# telemetry_box.net
KiCad netlist of a schematic drawn in EAGLE
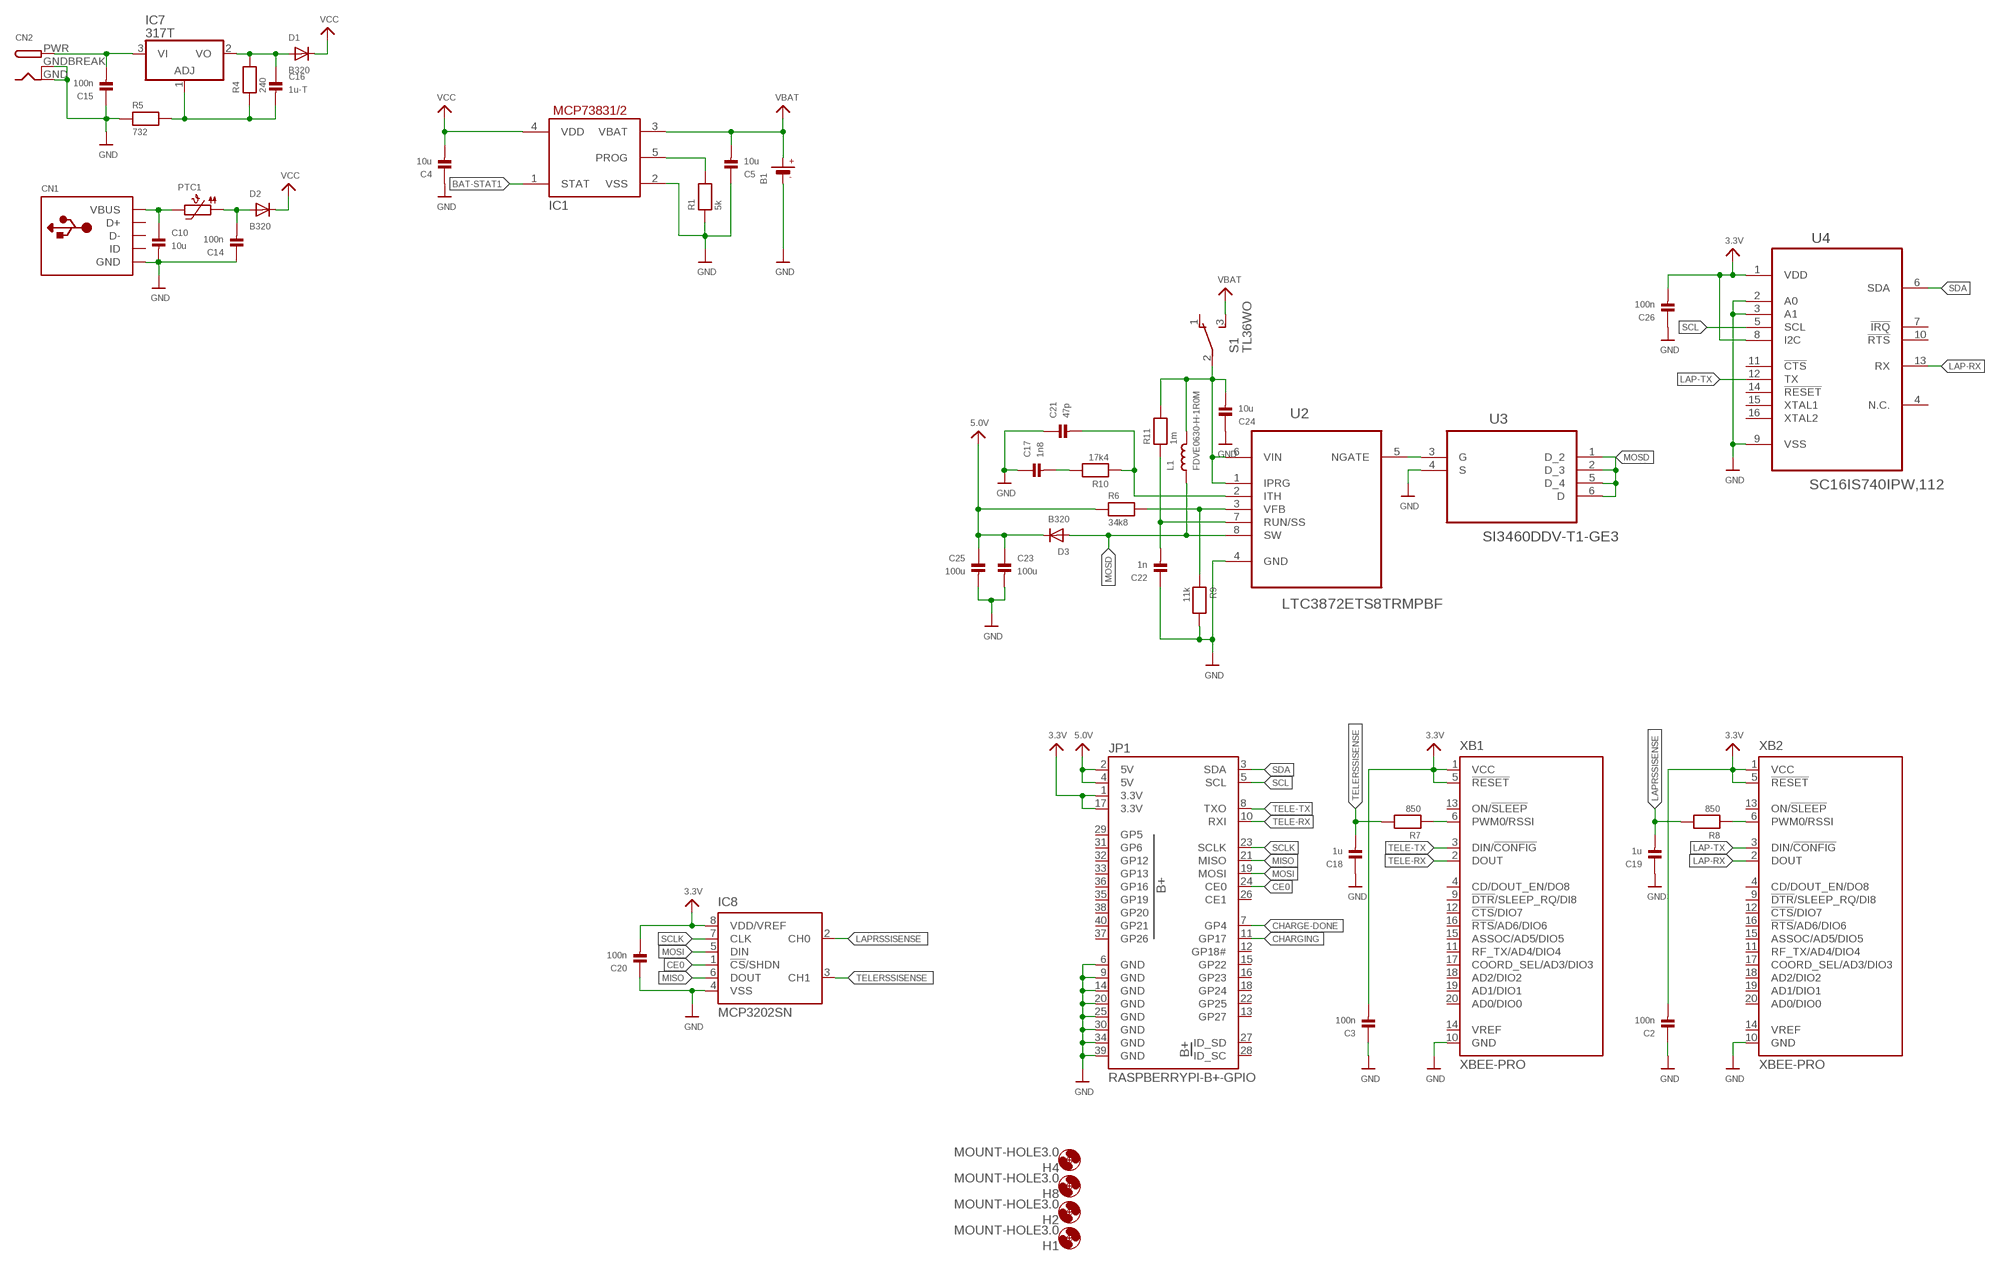
[diagram p0: schematic, sheet 1]

(export (version "E")
  (design (tool "Eeschema 10.0.6"))
  (components
    (comp (ref "B1")
      (value "BATTERY")
      (footprint "eagle-import:JSTPH2")
      (libsource (lib "eagle-import") (part "BATTERY"))
    )
    (comp (ref "C2")
      (value "100n")
      (footprint "eagle-import:_0603")
      (libsource (lib "eagle-import") (part "CAP_CERAMIC_0603"))
    )
    (comp (ref "C3")
      (value "100n")
      (footprint "eagle-import:_0603")
      (libsource (lib "eagle-import") (part "CAP_CERAMIC_0603"))
    )
    (comp (ref "C4")
      (value "10u")
      (footprint "eagle-import:_0805")
      (libsource (lib "eagle-import") (part "CAP_CERAMIC_0805"))
    )
    (comp (ref "C5")
      (value "10u")
      (footprint "eagle-import:_0805")
      (libsource (lib "eagle-import") (part "CAP_CERAMIC_0805"))
    )
    (comp (ref "C10")
      (value "10u")
      (footprint "eagle-import:_0805")
      (libsource (lib "eagle-import") (part "CAP_CERAMIC_0805"))
    )
    (comp (ref "C14")
      (value "100n")
      (footprint "eagle-import:_0603")
      (libsource (lib "eagle-import") (part "CAP_CERAMIC_0603"))
    )
    (comp (ref "C15")
      (value "100n")
      (footprint "eagle-import:_0603")
      (libsource (lib "eagle-import") (part "CAP_CERAMIC_0603"))
    )
    (comp (ref "C16")
      (value "1u-T")
      (footprint "eagle-import:_0603")
      (libsource (lib "eagle-import") (part "CAP_CERAMIC_0603"))
    )
    (comp (ref "C17")
      (value "1n8")
      (footprint "eagle-import:_0603")
      (libsource (lib "eagle-import") (part "CAP_CERAMIC_0603"))
    )
    (comp (ref "C18")
      (value "1u")
      (footprint "eagle-import:_0603")
      (libsource (lib "eagle-import") (part "CAP_CERAMIC_0603"))
    )
    (comp (ref "C19")
      (value "1u")
      (footprint "eagle-import:_0603")
      (libsource (lib "eagle-import") (part "CAP_CERAMIC_0603"))
    )
    (comp (ref "C20")
      (value "100n")
      (footprint "eagle-import:_0603")
      (libsource (lib "eagle-import") (part "CAP_CERAMIC_0603"))
    )
    (comp (ref "C21")
      (value "47p")
      (footprint "eagle-import:_0603")
      (libsource (lib "eagle-import") (part "CAP_CERAMIC_0603"))
    )
    (comp (ref "C22")
      (value "1n")
      (footprint "eagle-import:_0603")
      (libsource (lib "eagle-import") (part "CAP_CERAMIC_0603"))
    )
    (comp (ref "C23")
      (value "100u")
      (footprint "eagle-import:1206")
      (libsource (lib "eagle-import") (part "CAP_CERAMIC1206"))
    )
    (comp (ref "C24")
      (value "10u")
      (footprint "eagle-import:_0805")
      (libsource (lib "eagle-import") (part "CAP_CERAMIC_0805"))
    )
    (comp (ref "C25")
      (value "100u")
      (footprint "eagle-import:1206")
      (libsource (lib "eagle-import") (part "CAP_CERAMIC1206"))
    )
    (comp (ref "C26")
      (value "100n")
      (footprint "eagle-import:_0603")
      (libsource (lib "eagle-import") (part "CAP_CERAMIC_0603"))
    )
    (comp (ref "CN1")
      (value "USBMINIB")
      (footprint "eagle-import:USB-MINIB")
      (libsource (lib "eagle-import") (part "USBMINIB"))
    )
    (comp (ref "CN2")
      (value "DCBARRELPTH")
      (footprint "eagle-import:DCJACK_2MM_PTH")
      (libsource (lib "eagle-import") (part "DCBARRELPTH"))
    )
    (comp (ref "D1")
      (value "B320")
      (footprint "eagle-import:SMADIODE")
      (libsource (lib "eagle-import") (part "DIODESMA"))
    )
    (comp (ref "D2")
      (value "B320")
      (footprint "eagle-import:SMADIODE")
      (libsource (lib "eagle-import") (part "DIODESMA"))
    )
    (comp (ref "D3")
      (value "B320")
      (footprint "eagle-import:SMADIODE")
      (libsource (lib "eagle-import") (part "DIODESMA"))
    )
    (comp (ref "H1")
      (value "MOUNT-HOLE3.0")
      (footprint "eagle-import:3,0")
      (libsource (lib "eagle-import") (part "MOUNT-HOLE3.0"))
    )
    (comp (ref "H2")
      (value "MOUNT-HOLE3.0")
      (footprint "eagle-import:3,0")
      (libsource (lib "eagle-import") (part "MOUNT-HOLE3.0"))
    )
    (comp (ref "H4")
      (value "MOUNT-HOLE3.0")
      (footprint "eagle-import:3,0")
      (libsource (lib "eagle-import") (part "MOUNT-HOLE3.0"))
    )
    (comp (ref "H8")
      (value "MOUNT-HOLE3.0")
      (footprint "eagle-import:3,0")
      (libsource (lib "eagle-import") (part "MOUNT-HOLE3.0"))
    )
    (comp (ref "IC1")
      (value "MCP73831/OT")
      (footprint "eagle-import:SOT23-5L")
      (libsource (lib "eagle-import") (part "MCP73831/OT"))
    )
    (comp (ref "IC7")
      (value "317T")
      (footprint "eagle-import:TO220H")
      (libsource (lib "eagle-import") (part "317T"))
    )
    (comp (ref "IC8")
      (value "MCP3202SN")
      (footprint "eagle-import:SO-08")
      (fields (field (name "MF") "MICROCHIP") (field (name "MPN") "MCP3202-CI/SN"))
      (libsource (lib "eagle-import") (part "MCP3202SN"))
    )
    (comp (ref "JP1")
      (value "RASPBERRYPI-B+-GPIO")
      (footprint "eagle-import:2X20-SHROUDED")
      (libsource (lib "eagle-import") (part "RASPBERRYPI-B+-GPIO"))
    )
    (comp (ref "L1")
      (value "FDVE0630-H-1R0M")
      (footprint "eagle-import:INDUCTOR_6X6MM_TDK_SLF6045")
      (libsource (lib "eagle-import") (part "INDUCTORTDK_SLF6045"))
    )
    (comp (ref "PTC1")
      (value "PTC1206")
      (footprint "eagle-import:1206")
      (libsource (lib "eagle-import") (part "PTC1206"))
    )
    (comp (ref "R1")
      (value "5k")
      (footprint "eagle-import:_0603")
      (libsource (lib "eagle-import") (part "RESISTOR_0603"))
    )
    (comp (ref "R4")
      (value "240")
      (footprint "eagle-import:_0603")
      (libsource (lib "eagle-import") (part "RESISTOR_0603"))
    )
    (comp (ref "R5")
      (value "732")
      (footprint "eagle-import:_0603")
      (libsource (lib "eagle-import") (part "RESISTOR_0603"))
    )
    (comp (ref "R6")
      (value "34k8")
      (footprint "eagle-import:_0603")
      (libsource (lib "eagle-import") (part "RESISTOR_0603"))
    )
    (comp (ref "R7")
      (value "850")
      (footprint "eagle-import:_0603")
      (libsource (lib "eagle-import") (part "RESISTOR_0603"))
    )
    (comp (ref "R8")
      (value "850")
      (footprint "eagle-import:_0603")
      (libsource (lib "eagle-import") (part "RESISTOR_0603"))
    )
    (comp (ref "R9")
      (value "11k")
      (footprint "eagle-import:_0603")
      (libsource (lib "eagle-import") (part "RESISTOR_0603"))
    )
    (comp (ref "R10")
      (value "17k4")
      (footprint "eagle-import:_0603")
      (libsource (lib "eagle-import") (part "RESISTOR_0603"))
    )
    (comp (ref "R11")
      (value "1m")
      (footprint "eagle-import:_0603")
      (libsource (lib "eagle-import") (part "RESISTOR_0603"))
    )
    (comp (ref "S1")
      (value "TL36WO")
      (footprint "eagle-import:TL3XWO")
      (libsource (lib "eagle-import") (part "TL36WO"))
    )
    (comp (ref "U2")
      (value "LTC3872ETS8TRMPBF")
      (footprint "eagle-import:SOT65P280X100-8N")
      (fields (field (name "MPN") "LTC3872ETS8#TRMPBF"))
      (libsource (lib "eagle-import") (part "LTC3872ETS8TRMPBF"))
    )
    (comp (ref "U3")
      (value "SI3460DDV-T1-GE3")
      (footprint "eagle-import:SOT95P285X110-6N")
      (fields (field (name "MPN") "SI3457CDV-T1-GE3"))
      (libsource (lib "eagle-import") (part "SI3457CDV-T1-GE3"))
    )
    (comp (ref "U4")
      (value "SC16IS740IPW,112")
      (footprint "eagle-import:SOP65P640X110-16N")
      (libsource (lib "eagle-import") (part "SC16IS740IPW,112"))
    )
    (comp (ref "XB1")
      (value "XBEE-PRO")
      (footprint "eagle-import:XBEE-PRO")
      (libsource (lib "eagle-import") (part "XBEE-PRO"))
    )
    (comp (ref "XB2")
      (value "XBEE-PRO")
      (footprint "eagle-import:XBEE-PRO")
      (libsource (lib "eagle-import") (part "XBEE-PRO"))
    )
  )
  (nets
    (net (code "1") (name "3.3V") (class "Default")
      (node (ref "C2") (pin "2") (pinfunction "P$2_2") (pintype "passive"))
      (node (ref "C20") (pin "2") (pinfunction "P$2_2") (pintype "passive"))
      (node (ref "C26") (pin "2") (pinfunction "P$2_2") (pintype "passive"))
      (node (ref "C3") (pin "2") (pinfunction "P$2_2") (pintype "passive"))
      (node (ref "IC8") (pin "8") (pinfunction "VDD/VREF_8") (pintype "input"))
      (node (ref "JP1") (pin "1") (pinfunction "3.3V_1") (pintype "power_in"))
      (node (ref "JP1") (pin "17") (pinfunction "3.3V_17") (pintype "power_in"))
      (node (ref "U4") (pin "1") (pinfunction "VDD_1") (pintype "power_in"))
      (node (ref "U4") (pin "8") (pinfunction "I2C_8") (pintype "input"))
      (node (ref "XB1") (pin "1") (pinfunction "VCC_1") (pintype "power_in"))
      (node (ref "XB1") (pin "5") (pinfunction "~{RESET}_5") (pintype "input"))
      (node (ref "XB2") (pin "1") (pinfunction "VCC_1") (pintype "power_in"))
      (node (ref "XB2") (pin "5") (pinfunction "~{RESET}_5") (pintype "input"))
    )
    (net (code "2") (name "5.0V") (class "Default")
      (node (ref "C23") (pin "1") (pinfunction "P$1_1") (pintype "passive"))
      (node (ref "C25") (pin "1") (pinfunction "P$1_1") (pintype "passive"))
      (node (ref "D3") (pin "C") (pinfunction "C_C") (pintype "passive"))
      (node (ref "JP1") (pin "2") (pinfunction "5V_2") (pintype "power_in"))
      (node (ref "JP1") (pin "4") (pinfunction "5V_4") (pintype "power_in"))
      (node (ref "R6") (pin "1") (pinfunction "1_1") (pintype "passive"))
    )
    (net (code "3") (name "BAT-STAT1") (class "Default")
      (node (ref "IC1") (pin "1") (pinfunction "STAT_1") (pintype "output"))
    )
    (net (code "4") (name "CE0") (class "Default")
      (node (ref "IC8") (pin "1") (pinfunction "~{CS}/SHDN_1") (pintype "input"))
      (node (ref "JP1") (pin "24") (pinfunction "CE0_24") (pintype "output"))
    )
    (net (code "5") (name "CHARGE-DONE") (class "Default")
      (node (ref "JP1") (pin "7") (pinfunction "GP4_7") (pintype "bidirectional"))
    )
    (net (code "6") (name "CHARGING") (class "Default")
      (node (ref "JP1") (pin "11") (pinfunction "GP17_11") (pintype "bidirectional"))
    )
    (net (code "7") (name "GND") (class "Default")
      (node (ref "B1") (pin "1") (pinfunction "-_1") (pintype "passive"))
      (node (ref "C10") (pin "2") (pinfunction "P$2_2") (pintype "passive"))
      (node (ref "C14") (pin "1") (pinfunction "P$1_1") (pintype "passive"))
      (node (ref "C15") (pin "1") (pinfunction "P$1_1") (pintype "passive"))
      (node (ref "C17") (pin "1") (pinfunction "P$1_1") (pintype "passive"))
      (node (ref "C18") (pin "1") (pinfunction "P$1_1") (pintype "passive"))
      (node (ref "C19") (pin "1") (pinfunction "P$1_1") (pintype "passive"))
      (node (ref "C2") (pin "1") (pinfunction "P$1_1") (pintype "passive"))
      (node (ref "C20") (pin "1") (pinfunction "P$1_1") (pintype "passive"))
      (node (ref "C21") (pin "1") (pinfunction "P$1_1") (pintype "passive"))
      (node (ref "C22") (pin "1") (pinfunction "P$1_1") (pintype "passive"))
      (node (ref "C23") (pin "2") (pinfunction "P$2_2") (pintype "passive"))
      (node (ref "C24") (pin "1") (pinfunction "P$1_1") (pintype "passive"))
      (node (ref "C25") (pin "2") (pinfunction "P$2_2") (pintype "passive"))
      (node (ref "C26") (pin "1") (pinfunction "P$1_1") (pintype "passive"))
      (node (ref "C3") (pin "1") (pinfunction "P$1_1") (pintype "passive"))
      (node (ref "C4") (pin "1") (pinfunction "P$1_1") (pintype "passive"))
      (node (ref "C5") (pin "1") (pinfunction "P$1_1") (pintype "passive"))
      (node (ref "CN1") (pin "GND") (pinfunction "GND_GND") (pintype "power_in"))
      (node (ref "CN2") (pin "GND") (pinfunction "GND_GND") (pintype "power_in"))
      (node (ref "CN2") (pin "GNDBREAK") (pinfunction "GNDBREAK_GNDBREAK") (pintype "power_in"))
      (node (ref "IC1") (pin "2") (pinfunction "VSS_2") (pintype "power_in"))
      (node (ref "IC8") (pin "4") (pinfunction "VSS_4") (pintype "input"))
      (node (ref "JP1") (pin "14") (pinfunction "GND_14") (pintype "power_in"))
      (node (ref "JP1") (pin "20") (pinfunction "GND_20") (pintype "power_in"))
      (node (ref "JP1") (pin "25") (pinfunction "GND_25") (pintype "power_in"))
      (node (ref "JP1") (pin "30") (pinfunction "GND_30") (pintype "power_in"))
      (node (ref "JP1") (pin "34") (pinfunction "GND_34") (pintype "power_in"))
      (node (ref "JP1") (pin "39") (pinfunction "GND_39") (pintype "power_in"))
      (node (ref "JP1") (pin "6") (pinfunction "GND_6") (pintype "power_in"))
      (node (ref "JP1") (pin "9") (pinfunction "GND_9") (pintype "power_in"))
      (node (ref "R1") (pin "1") (pinfunction "1_1") (pintype "passive"))
      (node (ref "R5") (pin "1") (pinfunction "1_1") (pintype "passive"))
      (node (ref "R9") (pin "2") (pinfunction "2_2") (pintype "passive"))
      (node (ref "U2") (pin "4") (pinfunction "GND_4") (pintype "passive"))
      (node (ref "U3") (pin "4") (pinfunction "S_4") (pintype "passive"))
      (node (ref "U4") (pin "2") (pinfunction "A0_2") (pintype "input"))
      (node (ref "U4") (pin "3") (pinfunction "A1_3") (pintype "input"))
      (node (ref "U4") (pin "9") (pinfunction "VSS_9") (pintype "power_in"))
      (node (ref "XB1") (pin "10") (pinfunction "GND_10") (pintype "power_in"))
      (node (ref "XB2") (pin "10") (pinfunction "GND_10") (pintype "power_in"))
    )
    (net (code "8") (name "LAP-RX") (class "Default")
      (node (ref "U4") (pin "13") (pinfunction "RX_13") (pintype "output"))
      (node (ref "XB2") (pin "2") (pinfunction "DOUT_2") (pintype "output"))
    )
    (net (code "9") (name "LAP-TX") (class "Default")
      (node (ref "U4") (pin "12") (pinfunction "TX_12") (pintype "input"))
      (node (ref "XB2") (pin "3") (pinfunction "DIN/~{CONFIG}_3") (pintype "input"))
    )
    (net (code "10") (name "LAPRSSISENSE") (class "Default")
      (node (ref "C19") (pin "2") (pinfunction "P$2_2") (pintype "passive"))
      (node (ref "IC8") (pin "2") (pinfunction "CH0_2") (pintype "input"))
      (node (ref "R8") (pin "2") (pinfunction "2_2") (pintype "passive"))
    )
    (net (code "11") (name "MISO") (class "Default")
      (node (ref "IC8") (pin "6") (pinfunction "DOUT_6") (pintype "input"))
      (node (ref "JP1") (pin "21") (pinfunction "MISO_21") (pintype "input"))
    )
    (net (code "12") (name "MOSD") (class "Default")
      (node (ref "D3") (pin "A") (pinfunction "A_A") (pintype "passive"))
      (node (ref "L1") (pin "P$1") (pinfunction "1_P$1") (pintype "passive"))
      (node (ref "U2") (pin "8") (pinfunction "SW_8") (pintype "passive"))
      (node (ref "U3") (pin "1") (pinfunction "D_2_1") (pintype "passive"))
      (node (ref "U3") (pin "2") (pinfunction "D_3_2") (pintype "passive"))
      (node (ref "U3") (pin "5") (pinfunction "D_4_5") (pintype "passive"))
      (node (ref "U3") (pin "6") (pinfunction "D_6") (pintype "passive"))
    )
    (net (code "13") (name "MOSI") (class "Default")
      (node (ref "IC8") (pin "5") (pinfunction "DIN_5") (pintype "input"))
      (node (ref "JP1") (pin "19") (pinfunction "MOSI_19") (pintype "output"))
    )
    (net (code "14") (name "Net-(C10-P$1)") (class "Default")
      (node (ref "C10") (pin "1") (pinfunction "P$1_1") (pintype "passive"))
      (node (ref "CN1") (pin "VBUS") (pinfunction "VBUS_VBUS") (pintype "power_in"))
      (node (ref "PTC1") (pin "2") (pinfunction "2_2") (pintype "passive"))
    )
    (net (code "15") (name "Net-(C14-P$2)") (class "Default")
      (node (ref "C14") (pin "2") (pinfunction "P$2_2") (pintype "passive"))
      (node (ref "D2") (pin "A") (pinfunction "A_A") (pintype "passive"))
      (node (ref "PTC1") (pin "1") (pinfunction "1_1") (pintype "passive"))
    )
    (net (code "16") (name "Net-(C15-P$2)") (class "Default")
      (node (ref "C15") (pin "2") (pinfunction "P$2_2") (pintype "passive"))
      (node (ref "CN2") (pin "PWR") (pinfunction "PWR_PWR") (pintype "power_in"))
      (node (ref "IC7") (pin "3") (pinfunction "VI_3") (pintype "input"))
    )
    (net (code "17") (name "Net-(C16-P$1)") (class "Default")
      (node (ref "C16") (pin "1") (pinfunction "P$1_1") (pintype "passive"))
      (node (ref "D1") (pin "A") (pinfunction "A_A") (pintype "passive"))
      (node (ref "IC7") (pin "2") (pinfunction "VO_2") (pintype "passive"))
      (node (ref "R4") (pin "2") (pinfunction "2_2") (pintype "passive"))
    )
    (net (code "18") (name "Net-(C16-P$2)") (class "Default")
      (node (ref "C16") (pin "2") (pinfunction "P$2_2") (pintype "passive"))
      (node (ref "IC7") (pin "1") (pinfunction "ADJ_1") (pintype "input"))
      (node (ref "R4") (pin "1") (pinfunction "1_1") (pintype "passive"))
      (node (ref "R5") (pin "2") (pinfunction "2_2") (pintype "passive"))
    )
    (net (code "19") (name "Net-(C17-P$2)") (class "Default")
      (node (ref "C17") (pin "2") (pinfunction "P$2_2") (pintype "passive"))
      (node (ref "R10") (pin "2") (pinfunction "2_2") (pintype "passive"))
    )
    (net (code "20") (name "Net-(C21-P$2)") (class "Default")
      (node (ref "C21") (pin "2") (pinfunction "P$2_2") (pintype "passive"))
      (node (ref "R10") (pin "1") (pinfunction "1_1") (pintype "passive"))
      (node (ref "U2") (pin "2") (pinfunction "ITH_2") (pintype "input"))
    )
    (net (code "21") (name "Net-(C22-P$2)") (class "Default")
      (node (ref "C22") (pin "2") (pinfunction "P$2_2") (pintype "passive"))
      (node (ref "R11") (pin "1") (pinfunction "1_1") (pintype "passive"))
      (node (ref "U2") (pin "7") (pinfunction "RUN/SS_7") (pintype "input"))
    )
    (net (code "22") (name "Net-(C24-P$2)") (class "Default")
      (node (ref "C24") (pin "2") (pinfunction "P$2_2") (pintype "passive"))
      (node (ref "L1") (pin "P$2") (pinfunction "2_P$2") (pintype "passive"))
      (node (ref "R11") (pin "2") (pinfunction "2_2") (pintype "passive"))
      (node (ref "S1") (pin "2") (pinfunction "P_2") (pintype "passive"))
      (node (ref "U2") (pin "1") (pinfunction "IPRG_1") (pintype "input"))
      (node (ref "U2") (pin "6") (pinfunction "VIN_6") (pintype "power_in"))
    )
    (net (code "23") (name "Net-(IC1-PROG)") (class "Default")
      (node (ref "IC1") (pin "5") (pinfunction "PROG_5") (pintype "input"))
      (node (ref "R1") (pin "2") (pinfunction "2_2") (pintype "passive"))
    )
    (net (code "24") (name "Net-(U2-NGATE)") (class "Default")
      (node (ref "U2") (pin "5") (pinfunction "NGATE_5") (pintype "output"))
      (node (ref "U3") (pin "3") (pinfunction "G_3") (pintype "passive"))
    )
    (net (code "25") (name "Net-(U2-VFB)") (class "Default")
      (node (ref "R6") (pin "2") (pinfunction "2_2") (pintype "passive"))
      (node (ref "R9") (pin "1") (pinfunction "1_1") (pintype "passive"))
      (node (ref "U2") (pin "3") (pinfunction "VFB_3") (pintype "input"))
    )
    (net (code "26") (name "Net-(XB1-PWM0{slash}RSSI)") (class "Default")
      (node (ref "R7") (pin "1") (pinfunction "1_1") (pintype "passive"))
      (node (ref "XB1") (pin "6") (pinfunction "PWM0/RSSI_6") (pintype "output"))
    )
    (net (code "27") (name "Net-(XB2-PWM0{slash}RSSI)") (class "Default")
      (node (ref "R8") (pin "1") (pinfunction "1_1") (pintype "passive"))
      (node (ref "XB2") (pin "6") (pinfunction "PWM0/RSSI_6") (pintype "output"))
    )
    (net (code "28") (name "SCL") (class "Default")
      (node (ref "JP1") (pin "5") (pinfunction "SCL_5") (pintype "bidirectional"))
      (node (ref "U4") (pin "5") (pinfunction "SCL_5") (pintype "input"))
    )
    (net (code "29") (name "SCLK") (class "Default")
      (node (ref "IC8") (pin "7") (pinfunction "CLK_7") (pintype "input"))
      (node (ref "JP1") (pin "23") (pinfunction "SCLK_23") (pintype "output"))
    )
    (net (code "30") (name "SDA") (class "Default")
      (node (ref "JP1") (pin "3") (pinfunction "SDA_3") (pintype "bidirectional"))
      (node (ref "U4") (pin "6") (pinfunction "SDA_6") (pintype "bidirectional"))
    )
    (net (code "31") (name "TELE-RX") (class "Default")
      (node (ref "JP1") (pin "10") (pinfunction "RXI_10") (pintype "input"))
      (node (ref "XB1") (pin "2") (pinfunction "DOUT_2") (pintype "output"))
    )
    (net (code "32") (name "TELE-TX") (class "Default")
      (node (ref "JP1") (pin "8") (pinfunction "TXO_8") (pintype "output"))
      (node (ref "XB1") (pin "3") (pinfunction "DIN/~{CONFIG}_3") (pintype "input"))
    )
    (net (code "33") (name "TELERSSISENSE") (class "Default")
      (node (ref "C18") (pin "2") (pinfunction "P$2_2") (pintype "passive"))
      (node (ref "IC8") (pin "3") (pinfunction "CH1_3") (pintype "input"))
      (node (ref "R7") (pin "2") (pinfunction "2_2") (pintype "passive"))
    )
    (net (code "34") (name "VBAT") (class "Default")
      (node (ref "B1") (pin "2") (pinfunction "+_2") (pintype "passive"))
      (node (ref "C5") (pin "2") (pinfunction "P$2_2") (pintype "passive"))
      (node (ref "IC1") (pin "3") (pinfunction "VBAT_3") (pintype "bidirectional"))
      (node (ref "S1") (pin "3") (pinfunction "S_3") (pintype "passive"))
    )
    (net (code "35") (name "VCC") (class "Default")
      (node (ref "C4") (pin "2") (pinfunction "P$2_2") (pintype "passive"))
      (node (ref "D1") (pin "C") (pinfunction "C_C") (pintype "passive"))
      (node (ref "D2") (pin "C") (pinfunction "C_C") (pintype "passive"))
      (node (ref "IC1") (pin "4") (pinfunction "VDD_4") (pintype "power_in"))
    )
    (net (code "36") (name "unconnected-(CN1-PadD+)") (class "Default")
      (node (ref "CN1") (pin "D+") (pinfunction "D+_D+") (pintype "bidirectional"))
    )
    (net (code "37") (name "unconnected-(CN1-PadD-)") (class "Default")
      (node (ref "CN1") (pin "D-") (pinfunction "D-_D-") (pintype "bidirectional"))
    )
    (net (code "38") (name "unconnected-(CN1-PadID)") (class "Default")
      (node (ref "CN1") (pin "ID") (pinfunction "ID_ID") (pintype "bidirectional"))
    )
    (net (code "39") (name "unconnected-(JP1-CE1-Pad26)") (class "Default")
      (node (ref "JP1") (pin "26") (pinfunction "CE1_26") (pintype "output"))
    )
    (net (code "40") (name "unconnected-(JP1-GP5-Pad29)") (class "Default")
      (node (ref "JP1") (pin "29") (pinfunction "GP5_29") (pintype "bidirectional"))
    )
    (net (code "41") (name "unconnected-(JP1-GP6-Pad31)") (class "Default")
      (node (ref "JP1") (pin "31") (pinfunction "GP6_31") (pintype "bidirectional"))
    )
    (net (code "42") (name "unconnected-(JP1-GP12-Pad32)") (class "Default")
      (node (ref "JP1") (pin "32") (pinfunction "GP12_32") (pintype "bidirectional"))
    )
    (net (code "43") (name "unconnected-(JP1-GP13-Pad33)") (class "Default")
      (node (ref "JP1") (pin "33") (pinfunction "GP13_33") (pintype "bidirectional"))
    )
    (net (code "44") (name "unconnected-(JP1-GP16-Pad36)") (class "Default")
      (node (ref "JP1") (pin "36") (pinfunction "GP16_36") (pintype "bidirectional"))
    )
    (net (code "45") (name "unconnected-(JP1-GP18#-Pad12)") (class "Default")
      (node (ref "JP1") (pin "12") (pinfunction "GP18#_12") (pintype "bidirectional"))
    )
    (net (code "46") (name "unconnected-(JP1-GP19-Pad35)") (class "Default")
      (node (ref "JP1") (pin "35") (pinfunction "GP19_35") (pintype "bidirectional"))
    )
    (net (code "47") (name "unconnected-(JP1-GP20-Pad38)") (class "Default")
      (node (ref "JP1") (pin "38") (pinfunction "GP20_38") (pintype "bidirectional"))
    )
    (net (code "48") (name "unconnected-(JP1-GP21-Pad40)") (class "Default")
      (node (ref "JP1") (pin "40") (pinfunction "GP21_40") (pintype "bidirectional"))
    )
    (net (code "49") (name "unconnected-(JP1-GP22-Pad15)") (class "Default")
      (node (ref "JP1") (pin "15") (pinfunction "GP22_15") (pintype "bidirectional"))
    )
    (net (code "50") (name "unconnected-(JP1-GP23-Pad16)") (class "Default")
      (node (ref "JP1") (pin "16") (pinfunction "GP23_16") (pintype "bidirectional"))
    )
    (net (code "51") (name "unconnected-(JP1-GP24-Pad18)") (class "Default")
      (node (ref "JP1") (pin "18") (pinfunction "GP24_18") (pintype "bidirectional"))
    )
    (net (code "52") (name "unconnected-(JP1-GP25-Pad22)") (class "Default")
      (node (ref "JP1") (pin "22") (pinfunction "GP25_22") (pintype "bidirectional"))
    )
    (net (code "53") (name "unconnected-(JP1-GP26-Pad37)") (class "Default")
      (node (ref "JP1") (pin "37") (pinfunction "GP26_37") (pintype "bidirectional"))
    )
    (net (code "54") (name "unconnected-(JP1-GP27-Pad13)") (class "Default")
      (node (ref "JP1") (pin "13") (pinfunction "GP27_13") (pintype "bidirectional"))
    )
    (net (code "55") (name "unconnected-(JP1-ID_SC-Pad28)") (class "Default")
      (node (ref "JP1") (pin "28") (pinfunction "ID_SC_28") (pintype "bidirectional"))
    )
    (net (code "56") (name "unconnected-(JP1-ID_SD-Pad27)") (class "Default")
      (node (ref "JP1") (pin "27") (pinfunction "ID_SD_27") (pintype "bidirectional"))
    )
    (net (code "57") (name "unconnected-(S1-O-Pad1)") (class "Default")
      (node (ref "S1") (pin "1") (pinfunction "O_1") (pintype "passive"))
    )
    (net (code "58") (name "unconnected-(U4-N.C.-Pad4)") (class "Default")
      (node (ref "U4") (pin "4") (pinfunction "N.C._4") (pintype "no_connect"))
    )
    (net (code "59") (name "unconnected-(U4-XTAL1-Pad15)") (class "Default")
      (node (ref "U4") (pin "15") (pinfunction "XTAL1_15") (pintype "input"))
    )
    (net (code "60") (name "unconnected-(U4-XTAL2-Pad16)") (class "Default")
      (node (ref "U4") (pin "16") (pinfunction "XTAL2_16") (pintype "output"))
    )
    (net (code "61") (name "unconnected-(U4-~{CTS}-Pad11)") (class "Default")
      (node (ref "U4") (pin "11") (pinfunction "~{CTS}_11") (pintype "input"))
    )
    (net (code "62") (name "unconnected-(U4-~{IRQ}-Pad7)") (class "Default")
      (node (ref "U4") (pin "7") (pinfunction "~{IRQ}_7") (pintype "output"))
    )
    (net (code "63") (name "unconnected-(U4-~{RESET}-Pad14)") (class "Default")
      (node (ref "U4") (pin "14") (pinfunction "~{RESET}_14") (pintype "input"))
    )
    (net (code "64") (name "unconnected-(U4-~{RTS}-Pad10)") (class "Default")
      (node (ref "U4") (pin "10") (pinfunction "~{RTS}_10") (pintype "output"))
    )
    (net (code "65") (name "unconnected-(XB1-AD0{slash}DIO0-Pad20)") (class "Default")
      (node (ref "XB1") (pin "20") (pinfunction "AD0/DIO0_20") (pintype "bidirectional"))
    )
    (net (code "66") (name "unconnected-(XB1-AD1{slash}DIO1-Pad19)") (class "Default")
      (node (ref "XB1") (pin "19") (pinfunction "AD1/DIO1_19") (pintype "bidirectional"))
    )
    (net (code "67") (name "unconnected-(XB1-AD2{slash}DIO2-Pad18)") (class "Default")
      (node (ref "XB1") (pin "18") (pinfunction "AD2/DIO2_18") (pintype "bidirectional"))
    )
    (net (code "68") (name "unconnected-(XB1-ASSOC{slash}AD5{slash}DIO5-Pad15)") (class "Default")
      (node (ref "XB1") (pin "15") (pinfunction "ASSOC/AD5/DIO5_15") (pintype "bidirectional"))
    )
    (net (code "69") (name "unconnected-(XB1-CD{slash}DOUT_EN{slash}DO8-Pad4)") (class "Default")
      (node (ref "XB1") (pin "4") (pinfunction "CD/DOUT_EN/DO8_4") (pintype "output"))
    )
    (net (code "70") (name "unconnected-(XB1-COORD_SEL{slash}AD3{slash}DIO3-Pad17)") (class "Default")
      (node (ref "XB1") (pin "17") (pinfunction "COORD_SEL/AD3/DIO3_17") (pintype "bidirectional"))
    )
    (net (code "71") (name "unconnected-(XB1-ON{slash}~{SLEEP}-Pad13)") (class "Default")
      (node (ref "XB1") (pin "13") (pinfunction "ON/~{SLEEP}_13") (pintype "output"))
    )
    (net (code "72") (name "unconnected-(XB1-RF_TX{slash}AD4{slash}DIO4-Pad11)") (class "Default")
      (node (ref "XB1") (pin "11") (pinfunction "RF_TX/AD4/DIO4_11") (pintype "bidirectional"))
    )
    (net (code "73") (name "unconnected-(XB1-VREF-Pad14)") (class "Default")
      (node (ref "XB1") (pin "14") (pinfunction "VREF_14") (pintype "input"))
    )
    (net (code "74") (name "unconnected-(XB1-~{CTS}{slash}DIO7-Pad12)") (class "Default")
      (node (ref "XB1") (pin "12") (pinfunction "~{CTS}/DIO7_12") (pintype "bidirectional"))
    )
    (net (code "75") (name "unconnected-(XB1-~{DTR}{slash}SLEEP_RQ{slash}DI8-Pad9)") (class "Default")
      (node (ref "XB1") (pin "9") (pinfunction "~{DTR}/SLEEP_RQ/DI8_9") (pintype "bidirectional"))
    )
    (net (code "76") (name "unconnected-(XB1-~{RTS}{slash}AD6{slash}DIO6-Pad16)") (class "Default")
      (node (ref "XB1") (pin "16") (pinfunction "~{RTS}/AD6/DIO6_16") (pintype "bidirectional"))
    )
    (net (code "77") (name "unconnected-(XB2-AD0{slash}DIO0-Pad20)") (class "Default")
      (node (ref "XB2") (pin "20") (pinfunction "AD0/DIO0_20") (pintype "bidirectional"))
    )
    (net (code "78") (name "unconnected-(XB2-AD1{slash}DIO1-Pad19)") (class "Default")
      (node (ref "XB2") (pin "19") (pinfunction "AD1/DIO1_19") (pintype "bidirectional"))
    )
    (net (code "79") (name "unconnected-(XB2-AD2{slash}DIO2-Pad18)") (class "Default")
      (node (ref "XB2") (pin "18") (pinfunction "AD2/DIO2_18") (pintype "bidirectional"))
    )
    (net (code "80") (name "unconnected-(XB2-ASSOC{slash}AD5{slash}DIO5-Pad15)") (class "Default")
      (node (ref "XB2") (pin "15") (pinfunction "ASSOC/AD5/DIO5_15") (pintype "bidirectional"))
    )
    (net (code "81") (name "unconnected-(XB2-CD{slash}DOUT_EN{slash}DO8-Pad4)") (class "Default")
      (node (ref "XB2") (pin "4") (pinfunction "CD/DOUT_EN/DO8_4") (pintype "output"))
    )
    (net (code "82") (name "unconnected-(XB2-COORD_SEL{slash}AD3{slash}DIO3-Pad17)") (class "Default")
      (node (ref "XB2") (pin "17") (pinfunction "COORD_SEL/AD3/DIO3_17") (pintype "bidirectional"))
    )
    (net (code "83") (name "unconnected-(XB2-ON{slash}~{SLEEP}-Pad13)") (class "Default")
      (node (ref "XB2") (pin "13") (pinfunction "ON/~{SLEEP}_13") (pintype "output"))
    )
    (net (code "84") (name "unconnected-(XB2-RF_TX{slash}AD4{slash}DIO4-Pad11)") (class "Default")
      (node (ref "XB2") (pin "11") (pinfunction "RF_TX/AD4/DIO4_11") (pintype "bidirectional"))
    )
    (net (code "85") (name "unconnected-(XB2-VREF-Pad14)") (class "Default")
      (node (ref "XB2") (pin "14") (pinfunction "VREF_14") (pintype "input"))
    )
    (net (code "86") (name "unconnected-(XB2-~{CTS}{slash}DIO7-Pad12)") (class "Default")
      (node (ref "XB2") (pin "12") (pinfunction "~{CTS}/DIO7_12") (pintype "bidirectional"))
    )
    (net (code "87") (name "unconnected-(XB2-~{DTR}{slash}SLEEP_RQ{slash}DI8-Pad9)") (class "Default")
      (node (ref "XB2") (pin "9") (pinfunction "~{DTR}/SLEEP_RQ/DI8_9") (pintype "bidirectional"))
    )
    (net (code "88") (name "unconnected-(XB2-~{RTS}{slash}AD6{slash}DIO6-Pad16)") (class "Default")
      (node (ref "XB2") (pin "16") (pinfunction "~{RTS}/AD6/DIO6_16") (pintype "bidirectional"))
    )
  )
)
